# USB_CAN.net
KiCad netlist of a schematic drawn in Altium Designer
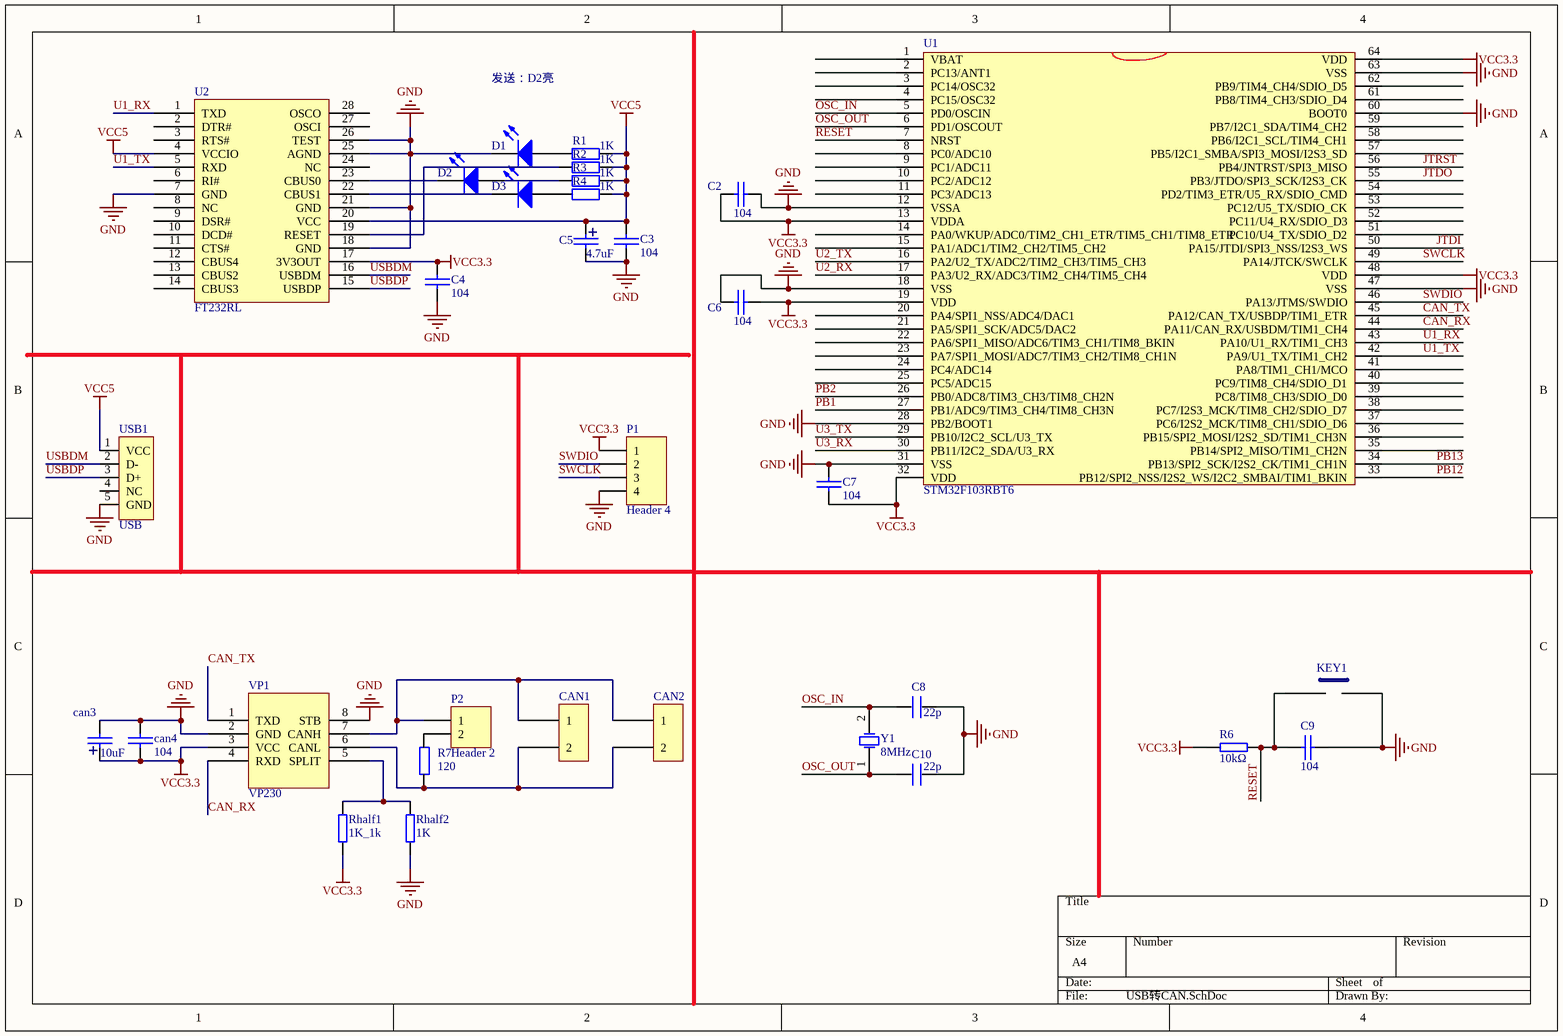
[diagram p0: USB转CAN.SchDoc]

(export (version "E")
  (design (tool "Eeschema 10.0.6"))
  (components
    (comp (ref "C2") (value "104") (footprint "0603P") (libsource (lib "main") (part "CAP_WYN")))
    (comp (ref "C3") (value "104") (footprint "0603P") (libsource (lib "main") (part "CAP_WYN")))
    (comp (ref "C4") (value "104") (footprint "0603P") (libsource (lib "main") (part "CAP_WYN")))
    (comp (ref "C5") (value "4.7uF") (footprint "1206") (libsource (lib "PCB_PROJECT1") (part "CAP_POL_WYN")))
    (comp (ref "C6") (value "104") (footprint "0603P") (libsource (lib "main") (part "CAP_WYN")))
    (comp (ref "C7") (value "104") (footprint "0603P") (libsource (lib "main") (part "CAP_WYN")))
    (comp (ref "C8") (value "22p") (footprint "0603P") (libsource (lib "探索者STM32F407封装库") (part "C")))
    (comp (ref "C9") (value "104") (footprint "0603P") (libsource (lib "main") (part "CAP_WYN")))
    (comp (ref "C10") (value "22p") (footprint "0603P") (libsource (lib "探索者STM32F407封装库") (part "C")))
    (comp (ref "CAN1") (value "2针端子") (footprint "CAN") (libsource (lib "library-1") (part "2针端子")))
    (comp (ref "CAN2") (value "2针端子") (footprint "CAN") (libsource (lib "library-1") (part "2针端子")))
    (comp (ref "can3")
      (value "10uF")
      (footprint "0603p")
      (libsource (lib "PCB_PROJECT1") (part "CAP_POL_WYN"))
    )
    (comp (ref "can4") (value "104") (footprint "0603p") (libsource (lib "main") (part "CAP_WYN")))
    (comp (ref "D1")
      (value "LED2")
      (footprint "SMDLED")
      (description "Typical RED, GREEN, YELLOW, AMBER GaAs LED")
      (fields (field (name "PUBLISHER") "Altium Limited"))
      (libsource (lib "Miscellaneous Devices") (part "LED2"))
    )
    (comp (ref "D2")
      (value "LED2")
      (footprint "SMDLED")
      (description "Typical RED, GREEN, YELLOW, AMBER GaAs LED")
      (fields (field (name "PUBLISHER") "Altium Limited"))
      (libsource (lib "Miscellaneous Devices") (part "LED2"))
    )
    (comp (ref "D3")
      (value "LED2")
      (footprint "SMDLED")
      (description "Typical RED, GREEN, YELLOW, AMBER GaAs LED")
      (fields (field (name "PUBLISHER") "Altium Limited"))
      (libsource (lib "Miscellaneous Devices") (part "LED2"))
    )
    (comp (ref "KEY1") (value "KEY2") (footprint "SW-PB") (libsource (lib "library-1") (part "KEY")))
    (comp (ref "P1")
      (value "Header 4")
      (footprint "HDR1X4")
      (description "Header, 4-Pin")
      (fields (field (name "PUBLISHER") "Altium Limited"))
      (libsource (lib "Miscellaneous Connectors") (part "Header 4"))
    )
    (comp (ref "P2")
      (value "Header 2")
      (footprint "HDR1X2")
      (description "Header, 2-Pin")
      (fields (field (name "PUBLISHER") "Altium Limited"))
      (libsource (lib "Miscellaneous Connectors") (part "Header 2"))
    )
    (comp (ref "R1")
      (value "1K")
      (footprint "0603P")
      (description "Resistor")
      (fields (field (name "Comment") "Res2") (field (name "PUBLISHER") "Altium Limited"))
      (libsource (lib "Miscellaneous Devices") (part "Res2"))
    )
    (comp (ref "R2")
      (value "1K")
      (footprint "0603P")
      (description "Resistor")
      (fields (field (name "Comment") "Res2") (field (name "PUBLISHER") "Altium Limited"))
      (libsource (lib "Miscellaneous Devices") (part "Res2"))
    )
    (comp (ref "R3")
      (value "1K")
      (footprint "0603P")
      (description "Resistor")
      (fields (field (name "Comment") "Res2") (field (name "PUBLISHER") "Altium Limited"))
      (libsource (lib "Miscellaneous Devices") (part "Res2"))
    )
    (comp (ref "R4")
      (value "1K")
      (footprint "0603P")
      (description "Resistor")
      (fields (field (name "Comment") "Res2") (field (name "PUBLISHER") "Altium Limited"))
      (libsource (lib "Miscellaneous Devices") (part "Res2"))
    )
    (comp (ref "R6") (value "10kΩ") (footprint "0603P") (libsource (lib "main") (part "RES_WYN")))
    (comp (ref "R7") (value "120") (footprint "0805") (libsource (lib "探索者STM32F407封装库") (part "R")))
    (comp (ref "Rhalf1")
      (value "1K_1k")
      (footprint "0603p")
      (libsource (lib "PCB_PROJECT1") (part "RES_WYN"))
    )
    (comp (ref "Rhalf2") (value "1K") (footprint "0603p") (libsource (lib "PCB_PROJECT1") (part "RES_WYN")))
    (comp (ref "U1")
      (value "STM32F103RBT6")
      (footprint "TQFP-64")
      (libsource (lib "stm32") (part "STM32F103RDT6"))
    )
    (comp (ref "U2") (value "FT232RL") (footprint "SSOP-28") (libsource (lib "my_library") (part "FT232RL")))
    (comp (ref "USB1") (value "USB") (footprint "USB") (libsource (lib "Schlib1") (part "USB")))
    (comp (ref "VP1") (value "VP230") (footprint "VP230") (libsource (lib "Schlib1") (part "VP230")))
    (comp (ref "Y1")
      (value "8MHz")
      (footprint "XTAL_US")
      (description "Crystal Oscillator")
      (fields (field (name "PUBLISHER") "Altium Limited"))
      (libsource (lib "探索者STM32F407封装库") (part "XTAL"))
    )
  )
  (nets
    (net (code "1") (name "/CAN_RX") (class "Default")
      (node (ref "U1") (pin "44") (pinfunction "PA11/CAN_RX/USBDM/TIM1_CH4_44") (pintype "passive"))
      (node (ref "VP1") (pin "4") (pinfunction "RXD_4") (pintype "passive"))
    )
    (net (code "2") (name "/CAN_TX") (class "Default")
      (node (ref "U1") (pin "45") (pinfunction "PA12/CAN_TX/USBDP/TIM1_ETR_45") (pintype "passive"))
      (node (ref "VP1") (pin "1") (pinfunction "TXD_1") (pintype "passive"))
    )
    (net (code "3") (name "/JTDI") (class "Default")
      (node (ref "U1") (pin "50") (pinfunction "PA15/JTDI/SPI3_NSS/I2S3_WS_50") (pintype "passive"))
    )
    (net (code "4") (name "/JTDO") (class "Default")
      (node (ref "U1") (pin "55") (pinfunction "PB3/JTDO/SPI3_SCK/I2S3_CK_55") (pintype "passive"))
    )
    (net (code "5") (name "/JTRST") (class "Default")
      (node (ref "U1") (pin "56") (pinfunction "PB4/JNTRST/SPI3_MISO_56") (pintype "passive"))
    )
    (net (code "6") (name "/OSC_IN") (class "Default")
      (node (ref "C8") (pin "1") (pintype "passive"))
      (node (ref "U1") (pin "5") (pinfunction "PD0/OSCIN_5") (pintype "passive"))
      (node (ref "Y1") (pin "2") (pinfunction "OSC2_2") (pintype "passive"))
    )
    (net (code "7") (name "/OSC_OUT") (class "Default")
      (node (ref "C10") (pin "1") (pintype "passive"))
      (node (ref "U1") (pin "6") (pinfunction "PD1/OSCOUT_6") (pintype "passive"))
      (node (ref "Y1") (pin "1") (pinfunction "OSC1_1") (pintype "passive"))
    )
    (net (code "8") (name "/PB1") (class "Default")
      (node (ref "U1") (pin "27") (pinfunction "PB1/ADC9/TIM3_CH4/TIM8_CH3N_27") (pintype "passive"))
    )
    (net (code "9") (name "/PB2") (class "Default")
      (node (ref "U1") (pin "26") (pinfunction "PB0/ADC8/TIM3_CH3/TIM8_CH2N_26") (pintype "passive"))
    )
    (net (code "10") (name "/PB12") (class "Default")
      (node (ref "U1") (pin "33") (pinfunction "PB12/SPI2_NSS/I2S2_WS/I2C2_SMBAI/TIM1_BKIN_33") (pintype "passive"))
    )
    (net (code "11") (name "/PB13") (class "Default")
      (node (ref "U1") (pin "34") (pinfunction "PB13/SPI2_SCK/I2S2_CK/TIM1_CH1N_34") (pintype "passive"))
    )
    (net (code "12") (name "/RESET") (class "Default")
      (node (ref "C9") (pin "1") (pintype "passive"))
      (node (ref "KEY1") (pin "2") (pinfunction "2_2") (pintype "passive"))
      (node (ref "R6") (pin "1") (pinfunction "1_1") (pintype "passive"))
      (node (ref "U1") (pin "7") (pinfunction "NRST_7") (pintype "passive"))
    )
    (net (code "13") (name "/SWCLK") (class "Default")
      (node (ref "P1") (pin "3") (pinfunction "3_3") (pintype "passive"))
      (node (ref "U1") (pin "49") (pinfunction "PA14/JTCK/SWCLK_49") (pintype "passive"))
    )
    (net (code "14") (name "/SWDIO") (class "Default")
      (node (ref "P1") (pin "2") (pinfunction "2_2") (pintype "passive"))
      (node (ref "U1") (pin "46") (pinfunction "PA13/JTMS/SWDIO_46") (pintype "passive"))
    )
    (net (code "15") (name "/U1_RX") (class "Default")
      (node (ref "U1") (pin "43") (pinfunction "PA10/U1_RX/TIM1_CH3_43") (pintype "passive"))
      (node (ref "U2") (pin "1") (pinfunction "TXD_1") (pintype "passive"))
    )
    (net (code "16") (name "/U1_TX") (class "Default")
      (node (ref "U1") (pin "42") (pinfunction "PA9/U1_TX/TIM1_CH2_42") (pintype "passive"))
      (node (ref "U2") (pin "5") (pinfunction "RXD_5") (pintype "passive"))
    )
    (net (code "17") (name "/U2_RX") (class "Default")
      (node (ref "U1") (pin "17") (pinfunction "PA3/U2_RX/ADC3/TIM2_CH4/TIM5_CH4_17") (pintype "passive"))
    )
    (net (code "18") (name "/U2_TX") (class "Default")
      (node (ref "U1") (pin "16") (pinfunction "PA2/U2_TX/ADC2/TIM2_CH3/TIM5_CH3_16") (pintype "passive"))
    )
    (net (code "19") (name "/U3_RX") (class "Default")
      (node (ref "U1") (pin "30") (pinfunction "PB11/I2C2_SDA/U3_RX_30") (pintype "passive"))
    )
    (net (code "20") (name "/U3_TX") (class "Default")
      (node (ref "U1") (pin "29") (pinfunction "PB10/I2C2_SCL/U3_TX_29") (pintype "passive"))
    )
    (net (code "21") (name "/USBDM") (class "Default")
      (node (ref "U2") (pin "16") (pinfunction "USBDM_16") (pintype "passive"))
      (node (ref "USB1") (pin "2") (pinfunction "D-_2") (pintype "passive"))
    )
    (net (code "22") (name "/USBDP") (class "Default")
      (node (ref "U2") (pin "15") (pinfunction "USBDP_15") (pintype "passive"))
      (node (ref "USB1") (pin "3") (pinfunction "D+_3") (pintype "passive"))
    )
    (net (code "23") (name "GND") (class "Default")
      (node (ref "C10") (pin "2") (pintype "passive"))
      (node (ref "C2") (pin "1") (pintype "passive"))
      (node (ref "C3") (pin "2") (pintype "passive"))
      (node (ref "C4") (pin "2") (pintype "passive"))
      (node (ref "C5") (pin "2") (pintype "passive"))
      (node (ref "C6") (pin "2") (pintype "passive"))
      (node (ref "C7") (pin "2") (pintype "passive"))
      (node (ref "C8") (pin "2") (pintype "passive"))
      (node (ref "C9") (pin "2") (pintype "passive"))
      (node (ref "D1") (pin "2") (pinfunction "K_2") (pintype "passive"))
      (node (ref "KEY1") (pin "1") (pinfunction "1_1") (pintype "passive"))
      (node (ref "P1") (pin "4") (pinfunction "4_4") (pintype "passive"))
      (node (ref "Rhalf2") (pin "1") (pinfunction "1_1") (pintype "passive"))
      (node (ref "U1") (pin "12") (pinfunction "VSSA_12") (pintype "passive"))
      (node (ref "U1") (pin "18") (pinfunction "VSS_18") (pintype "passive"))
      (node (ref "U1") (pin "28") (pinfunction "PB2/BOOT1_28") (pintype "passive"))
      (node (ref "U1") (pin "31") (pinfunction "VSS_31") (pintype "passive"))
      (node (ref "U1") (pin "47") (pinfunction "VSS_47") (pintype "passive"))
      (node (ref "U1") (pin "60") (pinfunction "BOOT0_60") (pintype "passive"))
      (node (ref "U1") (pin "63") (pinfunction "VSS_63") (pintype "passive"))
      (node (ref "U2") (pin "18") (pinfunction "GND_18") (pintype "passive"))
      (node (ref "U2") (pin "21") (pinfunction "GND_21") (pintype "passive"))
      (node (ref "U2") (pin "25") (pinfunction "AGND_25") (pintype "passive"))
      (node (ref "U2") (pin "26") (pinfunction "TEST_26") (pintype "passive"))
      (node (ref "U2") (pin "7") (pinfunction "GND_7") (pintype "passive"))
      (node (ref "USB1") (pin "5") (pinfunction "GND_5") (pintype "passive"))
      (node (ref "VP1") (pin "2") (pinfunction "GND_2") (pintype "passive"))
      (node (ref "VP1") (pin "8") (pinfunction "STB_8") (pintype "passive"))
      (node (ref "can3") (pin "2") (pintype "passive"))
      (node (ref "can4") (pin "1") (pintype "passive"))
    )
    (net (code "24") (name "Net-(D1-A)") (class "Default")
      (node (ref "D1") (pin "1") (pinfunction "A_1") (pintype "passive"))
      (node (ref "R1") (pin "1") (pinfunction "1_1") (pintype "passive"))
    )
    (net (code "25") (name "Net-(D2-A)") (class "Default")
      (node (ref "D2") (pin "1") (pinfunction "A_1") (pintype "passive"))
      (node (ref "R3") (pin "1") (pinfunction "1_1") (pintype "passive"))
    )
    (net (code "26") (name "Net-(D2-K)") (class "Default")
      (node (ref "D2") (pin "2") (pinfunction "K_2") (pintype "passive"))
      (node (ref "U2") (pin "23") (pinfunction "CBUS0_23") (pintype "passive"))
    )
    (net (code "27") (name "Net-(D3-A)") (class "Default")
      (node (ref "D3") (pin "1") (pinfunction "A_1") (pintype "passive"))
      (node (ref "R4") (pin "1") (pinfunction "1_1") (pintype "passive"))
    )
    (net (code "28") (name "Net-(D3-K)") (class "Default")
      (node (ref "D3") (pin "2") (pinfunction "K_2") (pintype "passive"))
      (node (ref "U2") (pin "22") (pinfunction "CBUS1_22") (pintype "passive"))
    )
    (net (code "29") (name "Net-(P2-Pad2)") (class "Default")
      (node (ref "P2") (pin "2") (pinfunction "2_2") (pintype "passive"))
      (node (ref "R7") (pin "2") (pintype "passive"))
    )
    (net (code "30") (name "Net-(U2-RESET)") (class "Default")
      (node (ref "R2") (pin "1") (pinfunction "1_1") (pintype "passive"))
      (node (ref "U2") (pin "19") (pinfunction "RESET_19") (pintype "passive"))
    )
    (net (code "31") (name "Net-(VP1-CANH)") (class "Default")
      (node (ref "CAN1") (pin "1") (pinfunction "1_1") (pintype "passive"))
      (node (ref "CAN2") (pin "1") (pinfunction "1_1") (pintype "passive"))
      (node (ref "P2") (pin "1") (pinfunction "1_1") (pintype "passive"))
      (node (ref "VP1") (pin "7") (pinfunction "CANH_7") (pintype "passive"))
    )
    (net (code "32") (name "Net-(VP1-CANL)") (class "Default")
      (node (ref "CAN1") (pin "2") (pinfunction "2_2") (pintype "passive"))
      (node (ref "CAN2") (pin "2") (pinfunction "2_2") (pintype "passive"))
      (node (ref "R7") (pin "1") (pintype "passive"))
      (node (ref "VP1") (pin "6") (pinfunction "CANL_6") (pintype "passive"))
    )
    (net (code "33") (name "Net-(VP1-SPLIT)") (class "Default")
      (node (ref "Rhalf1") (pin "2") (pinfunction "2_2") (pintype "passive"))
      (node (ref "Rhalf2") (pin "2") (pinfunction "2_2") (pintype "passive"))
      (node (ref "VP1") (pin "5") (pinfunction "SPLIT_5") (pintype "passive"))
    )
    (net (code "34") (name "VCC3.3") (class "Default")
      (node (ref "C2") (pin "2") (pintype "passive"))
      (node (ref "C4") (pin "1") (pintype "passive"))
      (node (ref "C6") (pin "1") (pintype "passive"))
      (node (ref "C7") (pin "1") (pintype "passive"))
      (node (ref "P1") (pin "1") (pinfunction "1_1") (pintype "passive"))
      (node (ref "R6") (pin "2") (pinfunction "2_2") (pintype "passive"))
      (node (ref "Rhalf1") (pin "1") (pinfunction "1_1") (pintype "passive"))
      (node (ref "U1") (pin "13") (pinfunction "VDDA_13") (pintype "passive"))
      (node (ref "U1") (pin "19") (pinfunction "VDD_19") (pintype "passive"))
      (node (ref "U1") (pin "32") (pinfunction "VDD_32") (pintype "passive"))
      (node (ref "U1") (pin "48") (pinfunction "VDD_48") (pintype "passive"))
      (node (ref "U1") (pin "64") (pinfunction "VDD_64") (pintype "passive"))
      (node (ref "U2") (pin "17") (pinfunction "3V3OUT_17") (pintype "passive"))
      (node (ref "VP1") (pin "3") (pinfunction "VCC_3") (pintype "passive"))
      (node (ref "can3") (pin "1") (pintype "passive"))
      (node (ref "can4") (pin "2") (pintype "passive"))
    )
    (net (code "35") (name "VCC5") (class "Default")
      (node (ref "C3") (pin "1") (pintype "passive"))
      (node (ref "C5") (pin "1") (pintype "passive"))
      (node (ref "R1") (pin "2") (pinfunction "2_2") (pintype "passive"))
      (node (ref "R2") (pin "2") (pinfunction "2_2") (pintype "passive"))
      (node (ref "R3") (pin "2") (pinfunction "2_2") (pintype "passive"))
      (node (ref "R4") (pin "2") (pinfunction "2_2") (pintype "passive"))
      (node (ref "U2") (pin "20") (pinfunction "VCC_20") (pintype "passive"))
      (node (ref "U2") (pin "4") (pinfunction "VCCIO_4") (pintype "passive"))
      (node (ref "USB1") (pin "1") (pinfunction "VCC_1") (pintype "passive"))
    )
    (net (code "36") (name "unconnected-(U1-PA0{slash}WKUP{slash}ADC0{slash}TIM2_CH1_ETR{slash}TIM5_CH1{slash}TIM8_ETR-Pad14)") (class "Default")
      (node (ref "U1") (pin "14") (pinfunction "PA0/WKUP/ADC0/TIM2_CH1_ETR/TIM5_CH1/TIM8_ETR_14") (pintype "passive"))
    )
    (net (code "37") (name "unconnected-(U1-PA1{slash}ADC1{slash}TIM2_CH2{slash}TIM5_CH2-Pad15)") (class "Default")
      (node (ref "U1") (pin "15") (pinfunction "PA1/ADC1/TIM2_CH2/TIM5_CH2_15") (pintype "passive"))
    )
    (net (code "38") (name "unconnected-(U1-PA4{slash}SPI1_NSS{slash}ADC4{slash}DAC1-Pad20)") (class "Default")
      (node (ref "U1") (pin "20") (pinfunction "PA4/SPI1_NSS/ADC4/DAC1_20") (pintype "passive"))
    )
    (net (code "39") (name "unconnected-(U1-PA5{slash}SPI1_SCK{slash}ADC5{slash}DAC2-Pad21)") (class "Default")
      (node (ref "U1") (pin "21") (pinfunction "PA5/SPI1_SCK/ADC5/DAC2_21") (pintype "passive"))
    )
    (net (code "40") (name "unconnected-(U1-PA6{slash}SPI1_MISO{slash}ADC6{slash}TIM3_CH1{slash}TIM8_BKIN-Pad22)") (class "Default")
      (node (ref "U1") (pin "22") (pinfunction "PA6/SPI1_MISO/ADC6/TIM3_CH1/TIM8_BKIN_22") (pintype "passive"))
    )
    (net (code "41") (name "unconnected-(U1-PA7{slash}SPI1_MOSI{slash}ADC7{slash}TIM3_CH2{slash}TIM8_CH1N-Pad23)") (class "Default")
      (node (ref "U1") (pin "23") (pinfunction "PA7/SPI1_MOSI/ADC7/TIM3_CH2/TIM8_CH1N_23") (pintype "passive"))
    )
    (net (code "42") (name "unconnected-(U1-PA8{slash}TIM1_CH1{slash}MCO-Pad41)") (class "Default")
      (node (ref "U1") (pin "41") (pinfunction "PA8/TIM1_CH1/MCO_41") (pintype "passive"))
    )
    (net (code "43") (name "unconnected-(U1-PB5{slash}I2C1_SMBA{slash}SPI3_MOSI{slash}I2S3_SD-Pad57)") (class "Default")
      (node (ref "U1") (pin "57") (pinfunction "PB5/I2C1_SMBA/SPI3_MOSI/I2S3_SD_57") (pintype "passive"))
    )
    (net (code "44") (name "unconnected-(U1-PB6{slash}I2C1_SCL{slash}TIM4_CH1-Pad58)") (class "Default")
      (node (ref "U1") (pin "58") (pinfunction "PB6/I2C1_SCL/TIM4_CH1_58") (pintype "passive"))
    )
    (net (code "45") (name "unconnected-(U1-PB7{slash}I2C1_SDA{slash}TIM4_CH2-Pad59)") (class "Default")
      (node (ref "U1") (pin "59") (pinfunction "PB7/I2C1_SDA/TIM4_CH2_59") (pintype "passive"))
    )
    (net (code "46") (name "unconnected-(U1-PB8{slash}TIM4_CH3{slash}SDIO_D4-Pad61)") (class "Default")
      (node (ref "U1") (pin "61") (pinfunction "PB8/TIM4_CH3/SDIO_D4_61") (pintype "passive"))
    )
    (net (code "47") (name "unconnected-(U1-PB9{slash}TIM4_CH4{slash}SDIO_D5-Pad62)") (class "Default")
      (node (ref "U1") (pin "62") (pinfunction "PB9/TIM4_CH4/SDIO_D5_62") (pintype "passive"))
    )
    (net (code "48") (name "unconnected-(U1-PB14{slash}SPI2_MISO{slash}TIM1_CH2N-Pad35)") (class "Default")
      (node (ref "U1") (pin "35") (pinfunction "PB14/SPI2_MISO/TIM1_CH2N_35") (pintype "passive"))
    )
    (net (code "49") (name "unconnected-(U1-PB15{slash}SPI2_MOSI{slash}I2S2_SD{slash}TIM1_CH3N-Pad36)") (class "Default")
      (node (ref "U1") (pin "36") (pinfunction "PB15/SPI2_MOSI/I2S2_SD/TIM1_CH3N_36") (pintype "passive"))
    )
    (net (code "50") (name "unconnected-(U1-PC0{slash}ADC10-Pad8)") (class "Default")
      (node (ref "U1") (pin "8") (pinfunction "PC0/ADC10_8") (pintype "passive"))
    )
    (net (code "51") (name "unconnected-(U1-PC1{slash}ADC11-Pad9)") (class "Default")
      (node (ref "U1") (pin "9") (pinfunction "PC1/ADC11_9") (pintype "passive"))
    )
    (net (code "52") (name "unconnected-(U1-PC2{slash}ADC12-Pad10)") (class "Default")
      (node (ref "U1") (pin "10") (pinfunction "PC2/ADC12_10") (pintype "passive"))
    )
    (net (code "53") (name "unconnected-(U1-PC3{slash}ADC13-Pad11)") (class "Default")
      (node (ref "U1") (pin "11") (pinfunction "PC3/ADC13_11") (pintype "passive"))
    )
    (net (code "54") (name "unconnected-(U1-PC4{slash}ADC14-Pad24)") (class "Default")
      (node (ref "U1") (pin "24") (pinfunction "PC4/ADC14_24") (pintype "passive"))
    )
    (net (code "55") (name "unconnected-(U1-PC5{slash}ADC15-Pad25)") (class "Default")
      (node (ref "U1") (pin "25") (pinfunction "PC5/ADC15_25") (pintype "passive"))
    )
    (net (code "56") (name "unconnected-(U1-PC6{slash}I2S2_MCK{slash}TIM8_CH1{slash}SDIO_D6-Pad37)") (class "Default")
      (node (ref "U1") (pin "37") (pinfunction "PC6/I2S2_MCK/TIM8_CH1/SDIO_D6_37") (pintype "passive"))
    )
    (net (code "57") (name "unconnected-(U1-PC7{slash}I2S3_MCK{slash}TIM8_CH2{slash}SDIO_D7-Pad38)") (class "Default")
      (node (ref "U1") (pin "38") (pinfunction "PC7/I2S3_MCK/TIM8_CH2/SDIO_D7_38") (pintype "passive"))
    )
    (net (code "58") (name "unconnected-(U1-PC8{slash}TIM8_CH3{slash}SDIO_D0-Pad39)") (class "Default")
      (node (ref "U1") (pin "39") (pinfunction "PC8/TIM8_CH3/SDIO_D0_39") (pintype "passive"))
    )
    (net (code "59") (name "unconnected-(U1-PC9{slash}TIM8_CH4{slash}SDIO_D1-Pad40)") (class "Default")
      (node (ref "U1") (pin "40") (pinfunction "PC9/TIM8_CH4/SDIO_D1_40") (pintype "passive"))
    )
    (net (code "60") (name "unconnected-(U1-PC10{slash}U4_TX{slash}SDIO_D2-Pad51)") (class "Default")
      (node (ref "U1") (pin "51") (pinfunction "PC10/U4_TX/SDIO_D2_51") (pintype "passive"))
    )
    (net (code "61") (name "unconnected-(U1-PC11{slash}U4_RX{slash}SDIO_D3-Pad52)") (class "Default")
      (node (ref "U1") (pin "52") (pinfunction "PC11/U4_RX/SDIO_D3_52") (pintype "passive"))
    )
    (net (code "62") (name "unconnected-(U1-PC12{slash}U5_TX{slash}SDIO_CK-Pad53)") (class "Default")
      (node (ref "U1") (pin "53") (pinfunction "PC12/U5_TX/SDIO_CK_53") (pintype "passive"))
    )
    (net (code "63") (name "unconnected-(U1-PC13{slash}ANT1-Pad2)") (class "Default")
      (node (ref "U1") (pin "2") (pinfunction "PC13/ANT1_2") (pintype "passive"))
    )
    (net (code "64") (name "unconnected-(U1-PC14{slash}OSC32-Pad3)") (class "Default")
      (node (ref "U1") (pin "3") (pinfunction "PC14/OSC32_3") (pintype "passive"))
    )
    (net (code "65") (name "unconnected-(U1-PC15{slash}OSC32-Pad4)") (class "Default")
      (node (ref "U1") (pin "4") (pinfunction "PC15/OSC32_4") (pintype "passive"))
    )
    (net (code "66") (name "unconnected-(U1-PD2{slash}TIM3_ETR{slash}U5_RX{slash}SDIO_CMD-Pad54)") (class "Default")
      (node (ref "U1") (pin "54") (pinfunction "PD2/TIM3_ETR/U5_RX/SDIO_CMD_54") (pintype "passive"))
    )
    (net (code "67") (name "unconnected-(U1-VBAT-Pad1)") (class "Default")
      (node (ref "U1") (pin "1") (pinfunction "VBAT_1") (pintype "passive"))
    )
    (net (code "68") (name "unconnected-(U2-CBUS2-Pad13)") (class "Default")
      (node (ref "U2") (pin "13") (pinfunction "CBUS2_13") (pintype "passive"))
    )
    (net (code "69") (name "unconnected-(U2-CBUS3-Pad14)") (class "Default")
      (node (ref "U2") (pin "14") (pinfunction "CBUS3_14") (pintype "passive"))
    )
    (net (code "70") (name "unconnected-(U2-CBUS4-Pad12)") (class "Default")
      (node (ref "U2") (pin "12") (pinfunction "CBUS4_12") (pintype "passive"))
    )
    (net (code "71") (name "unconnected-(U2-CTS#-Pad11)") (class "Default")
      (node (ref "U2") (pin "11") (pinfunction "CTS#_11") (pintype "passive"))
    )
    (net (code "72") (name "unconnected-(U2-DCD#-Pad10)") (class "Default")
      (node (ref "U2") (pin "10") (pinfunction "DCD#_10") (pintype "passive"))
    )
    (net (code "73") (name "unconnected-(U2-DSR#-Pad9)") (class "Default")
      (node (ref "U2") (pin "9") (pinfunction "DSR#_9") (pintype "passive"))
    )
    (net (code "74") (name "unconnected-(U2-DTR#-Pad2)") (class "Default")
      (node (ref "U2") (pin "2") (pinfunction "DTR#_2") (pintype "passive"))
    )
    (net (code "75") (name "unconnected-(U2-NC-Pad8)") (class "Default")
      (node (ref "U2") (pin "8") (pinfunction "NC_8") (pintype "passive"))
    )
    (net (code "76") (name "unconnected-(U2-NC-Pad24)") (class "Default")
      (node (ref "U2") (pin "24") (pinfunction "NC_24") (pintype "passive"))
    )
    (net (code "77") (name "unconnected-(U2-OSCI-Pad27)") (class "Default")
      (node (ref "U2") (pin "27") (pinfunction "OSCI_27") (pintype "passive"))
    )
    (net (code "78") (name "unconnected-(U2-OSCO-Pad28)") (class "Default")
      (node (ref "U2") (pin "28") (pinfunction "OSCO_28") (pintype "passive"))
    )
    (net (code "79") (name "unconnected-(U2-RI#-Pad6)") (class "Default")
      (node (ref "U2") (pin "6") (pinfunction "RI#_6") (pintype "passive"))
    )
    (net (code "80") (name "unconnected-(U2-RTS#-Pad3)") (class "Default")
      (node (ref "U2") (pin "3") (pinfunction "RTS#_3") (pintype "passive"))
    )
    (net (code "81") (name "unconnected-(USB1-NC-Pad4)") (class "Default")
      (node (ref "USB1") (pin "4") (pinfunction "NC_4") (pintype "passive"))
    )
  )
)
